# QSPIFlash.net
KiCad netlist of a schematic drawn in Altium Designer
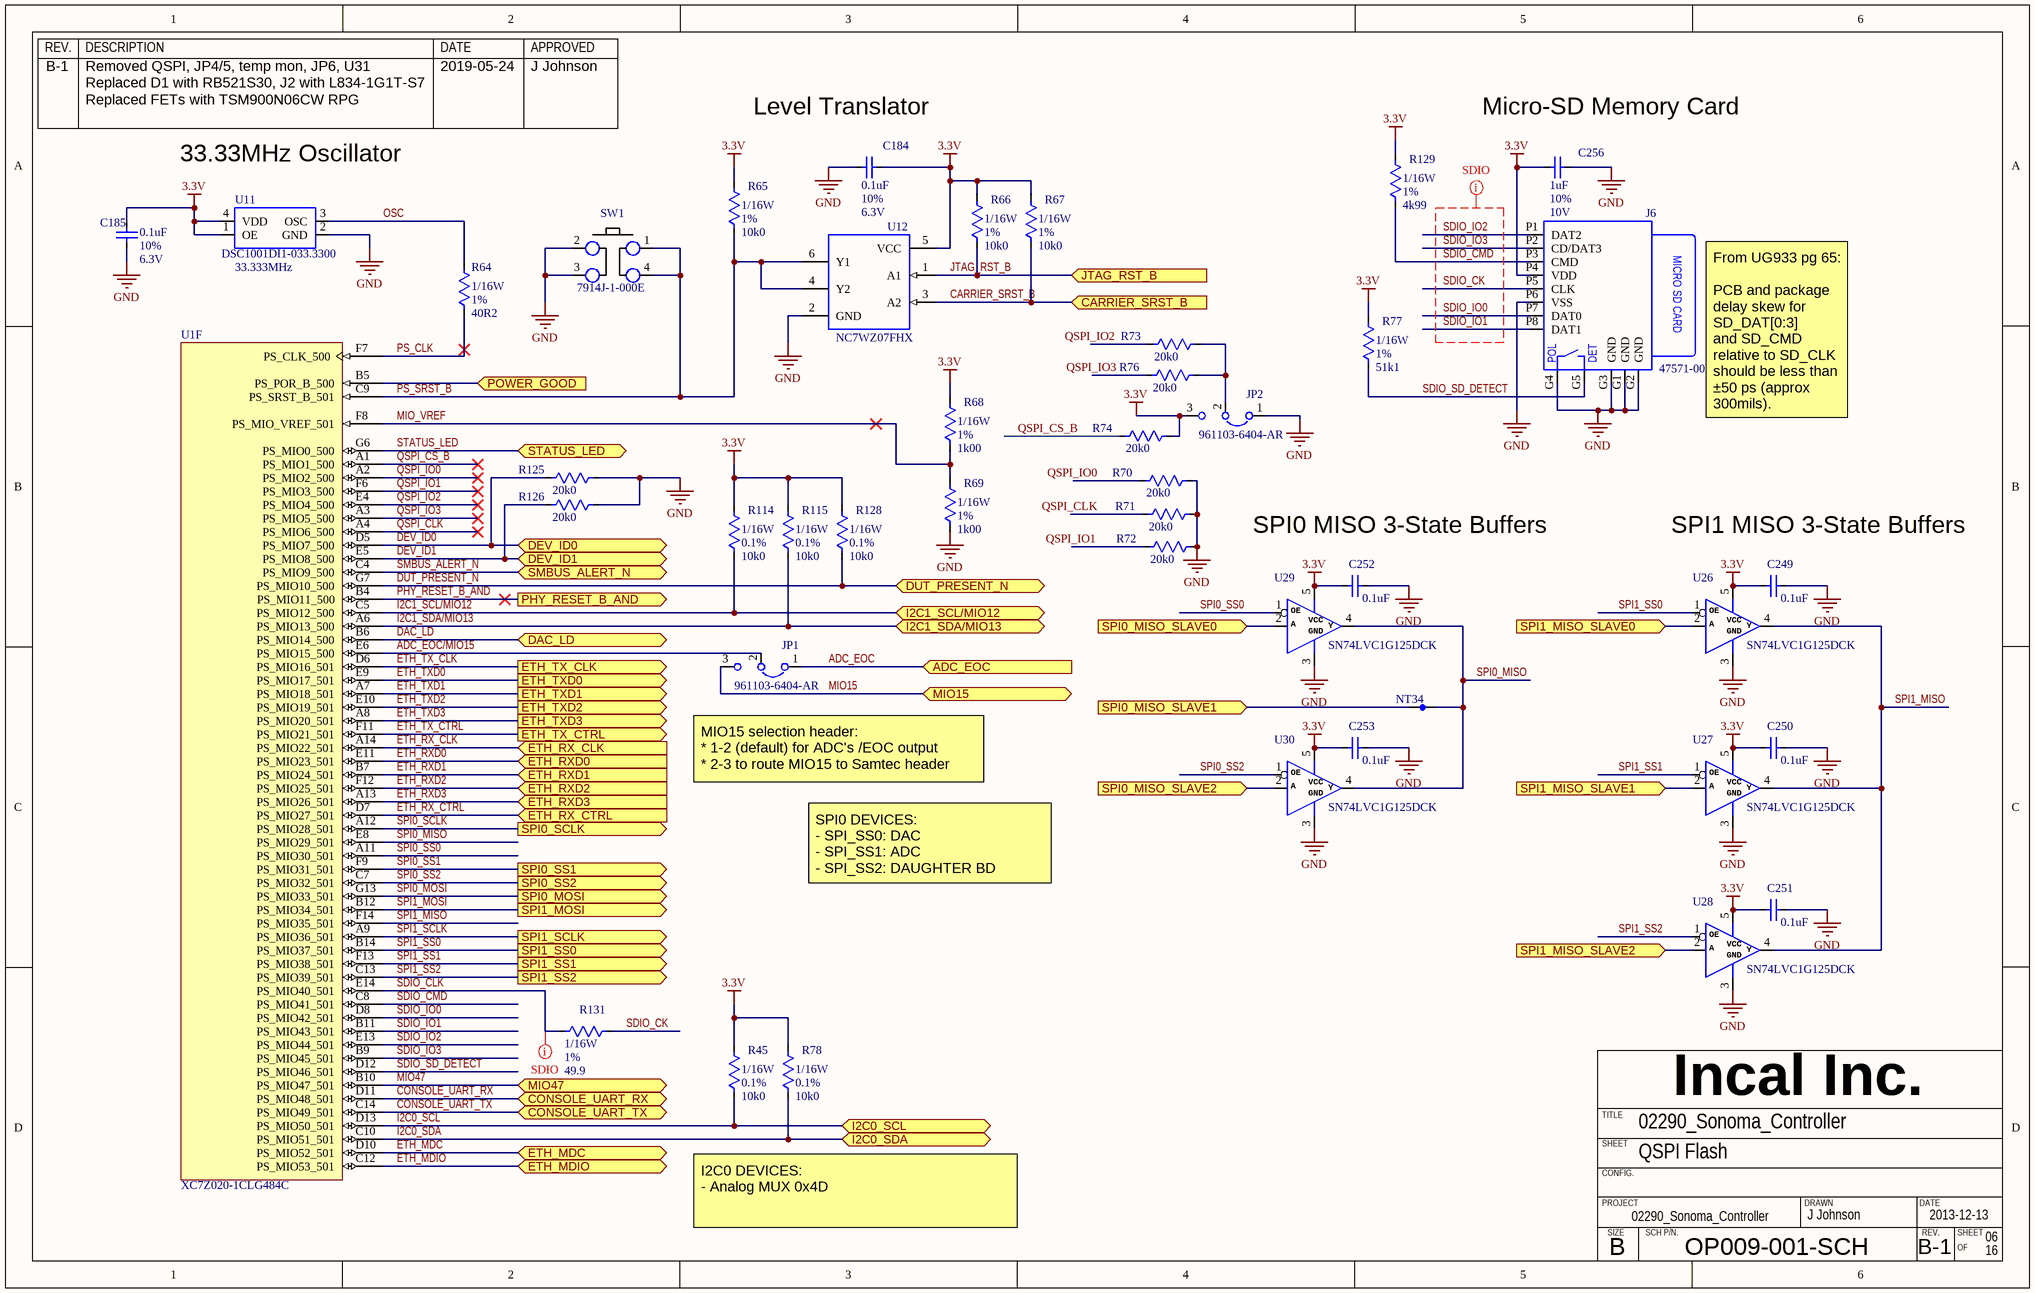
[diagram p0: QSPIFlash.SchDoc]

(export (version "E")
  (design (tool "Eeschema 10.0.6"))
  (components
    (comp (ref "C184")
      (value "0.1uF")
      (footprint "CAPC0603X33N")
      (description "Capacitor ceramic, X5R, 0.1uF, 6.3V, 10%, -55 to +125 C, EIA0201")
      (fields
        (field (name "TOLERANCE") "10%")
        (field (name "VOLTAGE") "6.3V")
        (field (name "Comment") "CAPACITOR_NP_TYPE1")
      )
      (libsource (lib "parts") (part "CAPACITOR_NP_TYPE1"))
    )
    (comp (ref "C185")
      (value "0.1uF")
      (footprint "CAPC0603X33N")
      (description "Capacitor ceramic, X5R, 0.1uF, 6.3V, 10%, -55 to +125 C, EIA0201")
      (fields
        (field (name "TOLERANCE") "10%")
        (field (name "VOLTAGE") "6.3V")
        (field (name "Comment") "CAPACITOR_NP_TYPE1")
      )
      (libsource (lib "parts") (part "CAPACITOR_NP_TYPE1"))
    )
    (comp (ref "C249")
      (value "0.1uF")
      (footprint "CAPC0603X33N")
      (description "Capacitor ceramic, X5R, 0.1uF, 6.3V, 10%, -55 to +125 C, EIA0201")
      (fields (field (name "TOLERANCE") "10%") (field (name "VOLTAGE") "6.3V"))
      (libsource (lib "parts") (part "CAPACITOR_NP_TYPE1"))
    )
    (comp (ref "C250")
      (value "0.1uF")
      (footprint "CAPC0603X33N")
      (description "Capacitor ceramic, X5R, 0.1uF, 6.3V, 10%, -55 to +125 C, EIA0201")
      (fields (field (name "TOLERANCE") "10%") (field (name "VOLTAGE") "6.3V"))
      (libsource (lib "parts") (part "CAPACITOR_NP_TYPE1"))
    )
    (comp (ref "C251")
      (value "0.1uF")
      (footprint "CAPC0603X33N")
      (description "Capacitor ceramic, X5R, 0.1uF, 6.3V, 10%, -55 to +125 C, EIA0201")
      (fields (field (name "TOLERANCE") "10%") (field (name "VOLTAGE") "6.3V"))
      (libsource (lib "parts") (part "CAPACITOR_NP_TYPE1"))
    )
    (comp (ref "C252")
      (value "0.1uF")
      (footprint "CAPC0603X33N")
      (description "Capacitor ceramic, X5R, 0.1uF, 6.3V, 10%, -55 to +125 C, EIA0201")
      (fields (field (name "TOLERANCE") "10%") (field (name "VOLTAGE") "6.3V"))
      (libsource (lib "parts") (part "CAPACITOR_NP_TYPE1"))
    )
    (comp (ref "C253")
      (value "0.1uF")
      (footprint "CAPC0603X33N")
      (description "Capacitor ceramic, X5R, 0.1uF, 6.3V, 10%, -55 to +125 C, EIA0201")
      (fields (field (name "TOLERANCE") "10%") (field (name "VOLTAGE") "6.3V"))
      (libsource (lib "parts") (part "CAPACITOR_NP_TYPE1"))
    )
    (comp (ref "C256")
      (value "1uF")
      (footprint "CAPC1005X33N")
      (description "Capacitor ceramic, X5R, 1uF, 10V, 10%, -55 to +85 C, EIA0402")
      (fields
        (field (name "TOLERANCE") "10%")
        (field (name "VOLTAGE") "10V")
        (field (name "Comment") "CAPACITOR_NP_TYPE1")
      )
      (libsource (lib "parts") (part "CAPACITOR_NP_TYPE1"))
    )
    (comp (ref "J6")
      (value "SD_MICRO_DET1")
      (footprint "47571-0001")
      (description "MicroSD Card Header with Detect, 9 pin, RA, 1.10 mm, SMT, -40 to +85C")
      (fields
        (field (name "POWER") "Pow")
        (field (name "VOLTAGE") "Vol")
        (field (name "MFG PART NUMBER 1") "47571-0001")
      )
      (libsource (lib "parts") (part "SD_MICRO_DET1"))
    )
    (comp (ref "JP1")
      (value "JP_HDR3x1_DEF1")
      (footprint "JMPR3P254_SHUNT12")
      (description "Jumper Header .100'', 3-pin, Default position 1-2, TH")
      (fields
        (field (name "POWER") "Pow")
        (field (name "VOLTAGE") "Vol")
        (field (name "MFG PART NUMBER 1") "961103-6404-AR")
      )
      (libsource (lib "parts") (part "JP_HDR3x1_DEF1"))
    )
    (comp (ref "JP2")
      (value "JP_HDR3x1_DEF1")
      (footprint "3PIN_HEADER")
      (description "Jumper Header .100'', 3-pin, Default position 1-2, TH")
      (fields
        (field (name "POWER") "Pow")
        (field (name "VOLTAGE") "Vol")
        (field (name "MFG PART NUMBER 1") "961103-6404-AR")
      )
      (libsource (lib "parts") (part "JP_HDR3x1_DEF1"))
    )
    (comp (ref "NT34")
      (value "NET_TIE_1X1")
      (footprint "NET_TIE_1X1")
      (description "Net Tie 1 to 1")
      (libsource (lib "parts") (part "NET_TIE_1X1"))
    )
    (comp (ref "R45")
      (value "10k0")
      (footprint "RESC1005X33N")
      (description "Resistor, 10k0, 1/16W, 0.1%, -50 to +155 C, EIA0402")
      (fields (field (name "VOLTAGE") "50V") (field (name "POWER") "1/16W") (field (name "TOLERANCE") "0.1%"))
      (libsource (lib "parts") (part "RESISTOR_TYPE1"))
    )
    (comp (ref "R64")
      (value "40R2")
      (footprint "RESC1005X33N")
      (description "Resistor, 40R2, 1/16W, 1%, -50 to +155 C, EIA0402, EIA(M)1005")
      (fields (field (name "VOLTAGE") "50V") (field (name "POWER") "1/16W") (field (name "TOLERANCE") "1%"))
      (libsource (lib "parts") (part "RESISTOR_TYPE1"))
    )
    (comp (ref "R65")
      (value "10k0")
      (footprint "RESC1005X33N")
      (description "Resistor, 10k0, 1/16W, 1%, -55 to +155 C, EIA0402")
      (fields (field (name "VOLTAGE") "50V") (field (name "POWER") "1/16W") (field (name "TOLERANCE") "1%"))
      (libsource (lib "parts") (part "RESISTOR_TYPE1"))
    )
    (comp (ref "R66")
      (value "10k0")
      (footprint "RESC1005X33N")
      (description "Resistor, 10k0, 1/16W, 1%, -55 to +155 C, EIA0402")
      (fields (field (name "VOLTAGE") "50V") (field (name "POWER") "1/16W") (field (name "TOLERANCE") "1%"))
      (libsource (lib "parts") (part "RESISTOR_TYPE1"))
    )
    (comp (ref "R67")
      (value "10k0")
      (footprint "RESC1005X33N")
      (description "Resistor, 10k0, 1/16W, 1%, -55 to +155 C, EIA0402")
      (fields (field (name "VOLTAGE") "50V") (field (name "POWER") "1/16W") (field (name "TOLERANCE") "1%"))
      (libsource (lib "parts") (part "RESISTOR_TYPE1"))
    )
    (comp (ref "R68")
      (value "1k00")
      (footprint "RESC1005X33N")
      (description "Resistor, 1k00, 1/16W, 1%, -55 to +155 C, EIA0402")
      (fields (field (name "VOLTAGE") "50V") (field (name "POWER") "1/16W") (field (name "TOLERANCE") "1%"))
      (libsource (lib "parts") (part "RESISTOR_TYPE1"))
    )
    (comp (ref "R69")
      (value "1k00")
      (footprint "RESC1005X33N")
      (description "Resistor, 1k00, 1/16W, 1%, -55 to +155 C, EIA0402")
      (fields (field (name "VOLTAGE") "50V") (field (name "POWER") "1/16W") (field (name "TOLERANCE") "1%"))
      (libsource (lib "parts") (part "RESISTOR_TYPE1"))
    )
    (comp (ref "R70")
      (value "20k0")
      (footprint "0402")
      (description "Resistor, 20k0, 1/16W, 1%, -50 to +155 C, EIA0402, EIA(M)1005")
      (fields (field (name "VOLTAGE") "50V") (field (name "POWER") "1/16W"))
      (libsource (lib "parts") (part "RESISTOR_TYPE1"))
    )
    (comp (ref "R71")
      (value "20k0")
      (footprint "0402")
      (description "Resistor, 20k0, 1/16W, 1%, -50 to +155 C, EIA0402, EIA(M)1005")
      (fields (field (name "VOLTAGE") "50V") (field (name "POWER") "1/16W"))
      (libsource (lib "parts") (part "RESISTOR_TYPE1"))
    )
    (comp (ref "R72")
      (value "20k0")
      (footprint "RESC1005X33N")
      (description "Resistor, 20k0, 1/16W, 1%, -50 to +155 C, EIA0402, EIA(M)1005")
      (fields (field (name "VOLTAGE") "50V") (field (name "POWER") "1/16W"))
      (libsource (lib "parts") (part "RESISTOR_TYPE1"))
    )
    (comp (ref "R73")
      (value "20k0")
      (footprint "0402")
      (description "Resistor, 20k0, 1/16W, 1%, -50 to +155 C, EIA0402, EIA(M)1005")
      (fields (field (name "VOLTAGE") "50V") (field (name "POWER") "1/16W"))
      (libsource (lib "parts") (part "RESISTOR_TYPE1"))
    )
    (comp (ref "R74")
      (value "20k0")
      (footprint "0402")
      (description "Resistor, 20k0, 1/16W, 1%, -50 to +155 C, EIA0402, EIA(M)1005")
      (fields (field (name "VOLTAGE") "50V") (field (name "POWER") "1/16W"))
      (libsource (lib "parts") (part "RESISTOR_TYPE1"))
    )
    (comp (ref "R76")
      (value "20k0")
      (footprint "0402")
      (description "Resistor, 20k0, 1/16W, 1%, -50 to +155 C, EIA0402, EIA(M)1005")
      (fields (field (name "VOLTAGE") "50V") (field (name "POWER") "1/16W"))
      (libsource (lib "parts") (part "RESISTOR_TYPE1"))
    )
    (comp (ref "R77")
      (value "51k1")
      (footprint "RESC1005X33N")
      (description "Resistor, 51k1, 1/16W, 1%, -50 to +155 C, EIA0402, EIA(M)1005")
      (fields (field (name "VOLTAGE") "50V") (field (name "POWER") "1/16W") (field (name "TOLERANCE") "1%"))
      (libsource (lib "parts") (part "RESISTOR_TYPE1"))
    )
    (comp (ref "R78")
      (value "10k0")
      (footprint "RESC1005X33N")
      (description "Resistor, 10k0, 1/16W, 0.1%, -50 to +155 C, EIA0402")
      (fields (field (name "VOLTAGE") "50V") (field (name "POWER") "1/16W") (field (name "TOLERANCE") "0.1%"))
      (libsource (lib "parts") (part "RESISTOR_TYPE1"))
    )
    (comp (ref "R114")
      (value "10k0")
      (footprint "RESC1005X33N")
      (description "Resistor, 10k0, 1/16W, 0.1%, -50 to +155 C, EIA0402")
      (fields (field (name "VOLTAGE") "50V") (field (name "POWER") "1/16W") (field (name "TOLERANCE") "0.1%"))
      (libsource (lib "parts") (part "RESISTOR_TYPE1"))
    )
    (comp (ref "R115")
      (value "10k0")
      (footprint "RESC1005X33N")
      (description "Resistor, 10k0, 1/16W, 0.1%, -50 to +155 C, EIA0402")
      (fields (field (name "VOLTAGE") "50V") (field (name "POWER") "1/16W") (field (name "TOLERANCE") "0.1%"))
      (libsource (lib "parts") (part "RESISTOR_TYPE1"))
    )
    (comp (ref "R125")
      (value "20k0")
      (footprint "RESC1005X33N")
      (description "Resistor, 20k0, 1/16W, 1%, -50 to +155 C, EIA0402, EIA(M)1005")
      (fields (field (name "VOLTAGE") "50V") (field (name "POWER") "1/16W"))
      (libsource (lib "parts") (part "RESISTOR_TYPE1"))
    )
    (comp (ref "R126")
      (value "20k0")
      (footprint "RESC1005X33N")
      (description "Resistor, 20k0, 1/16W, 1%, -50 to +155 C, EIA0402, EIA(M)1005")
      (fields (field (name "VOLTAGE") "50V") (field (name "POWER") "1/16W"))
      (libsource (lib "parts") (part "RESISTOR_TYPE1"))
    )
    (comp (ref "R128")
      (value "10k0")
      (footprint "RESC1005X33N")
      (description "Resistor, 10k0, 1/16W, 0.1%, -50 to +155 C, EIA0402")
      (fields (field (name "VOLTAGE") "50V") (field (name "POWER") "1/16W") (field (name "TOLERANCE") "0.1%"))
      (libsource (lib "parts") (part "RESISTOR_TYPE1"))
    )
    (comp (ref "R129")
      (value "4k99")
      (footprint "RESC1005X33N")
      (description "Resistor, 4k99, 1/16W, 1%, -50 to +155 C, EIA0402, EIA(M)1005")
      (fields (field (name "VOLTAGE") "50V") (field (name "POWER") "1/16W") (field (name "TOLERANCE") "1%"))
      (libsource (lib "parts") (part "RESISTOR_TYPE1"))
    )
    (comp (ref "R131")
      (value "49.9")
      (footprint "RESC1005X33N")
      (description "Resistor, 51k1, 1/16W, 1%, -50 to +155 C, EIA0402, EIA(M)1005")
      (fields (field (name "VOLTAGE") "50V") (field (name "POWER") "1/16W") (field (name "TOLERANCE") "1%"))
      (libsource (lib "parts") (part "RESISTOR_TYPE1"))
    )
    (comp (ref "SW1")
      (value "7914J-1-000E")
      (footprint "7914J-1-000E")
      (description "Switch, tactile, 39V, 4mm, -55 to +125 C, SMD")
      (fields (field (name "POWER") "Pow") (field (name "VOLTAGE") "39V"))
      (libsource (lib "parts") (part "SW_SPST_TYPE1"))
    )
    (comp (ref "U1")
      (value "XC7Z020-1CLG484C")
      (footprint "CLG484")
      (description "667 MHz Zynq™-7000 AP SoC, 130 PS I/O, 200 FPGA I/O, 484-Ball BGA, Speed Grade 1, Commercial Grade")
      (fields (field (name "GENERIC PART NUMBER") "XC7Z020") (field (name "MANUFACTURER") "Xilinx"))
      (libsource (lib "parts") (part "XC7Z020-1CLG484C"))
    )
    (comp (ref "U11")
      (value "33.333MHz")
      (footprint "OSCSC165P200X250X85-4N")
      (description "Oscillator, CMOS, 33.333MHz, 50ppm, 1.7V to 3.6V, -40 to +85C, SMT")
      (fields
        (field (name "VOLTAGE") "1.7V to 3.6V")
        (field (name "MFG PART NUMBER 1") "DSC1001DI1-033.3300")
        (field (name "Comment") "OSCILLATOR_TYPE1")
      )
      (libsource (lib "parts") (part "OSCILLATOR_TYPE1"))
    )
    (comp (ref "U12")
      (value "NC7WZ07FHX")
      (footprint "DFN35P100X100X55-6N")
      (description "UHS Dual Buffer, Tiny Logic, 1.65 to 5.5V, -40 to +85 C, 200mW, MicroPak2-6")
      (fields
        (field (name "POWER") "Pow")
        (field (name "VOLTAGE") "1.65 to 5.5V")
        (field (name "MFG PART NUMBER 1") "NC7WZ07FHX")
      )
      (libsource (lib "parts") (part "NC7WZ07FHX"))
    )
    (comp (ref "U26")
      (value "SN74LVC1G125DCK")
      (footprint "SOT65P210X110-5N")
      (description "Tristate buffer, 1.65 to 5.5V, +/- 24mA, -40 to +125 C, 150mW, SC70")
      (fields (field (name "POWER") "150mW") (field (name "VOLTAGE") "1.65 to 5.5V"))
      (libsource (lib "parts") (part "TINY_SCHM_BUF_TRIS_TYPE1"))
    )
    (comp (ref "U27")
      (value "SN74LVC1G125DCK")
      (footprint "SOT65P210X110-5N")
      (description "Tristate buffer, 1.65 to 5.5V, +/- 24mA, -40 to +125 C, 150mW, SC70")
      (fields (field (name "POWER") "150mW") (field (name "VOLTAGE") "1.65 to 5.5V"))
      (libsource (lib "parts") (part "TINY_SCHM_BUF_TRIS_TYPE1"))
    )
    (comp (ref "U28")
      (value "SN74LVC1G125DCK")
      (footprint "SOT65P210X110-5N")
      (description "Tristate buffer, 1.65 to 5.5V, +/- 24mA, -40 to +125 C, 150mW, SC70")
      (fields (field (name "POWER") "150mW") (field (name "VOLTAGE") "1.65 to 5.5V"))
      (libsource (lib "parts") (part "TINY_SCHM_BUF_TRIS_TYPE1"))
    )
    (comp (ref "U29")
      (value "SN74LVC1G125DCK")
      (footprint "SOT65P210X110-5N")
      (description "Tristate buffer, 1.65 to 5.5V, +/- 24mA, -40 to +125 C, 150mW, SC70")
      (fields (field (name "POWER") "150mW") (field (name "VOLTAGE") "1.65 to 5.5V"))
      (libsource (lib "parts") (part "TINY_SCHM_BUF_TRIS_TYPE1"))
    )
    (comp (ref "U30")
      (value "SN74LVC1G125DCK")
      (footprint "SOT65P210X110-5N")
      (description "Tristate buffer, 1.65 to 5.5V, +/- 24mA, -40 to +125 C, 150mW, SC70")
      (fields (field (name "POWER") "150mW") (field (name "VOLTAGE") "1.65 to 5.5V"))
      (libsource (lib "parts") (part "TINY_SCHM_BUF_TRIS_TYPE1"))
    )
  )
  (nets
    (net (code "1") (name "/ADC_EOC") (class "Default") (node (ref "JP1") (pin "1") (pintype "passive")))
    (net (code "2") (name "/ADC_EOC{slash}MIO15") (class "Default")
      (node (ref "JP1") (pin "2") (pintype "passive"))
      (node (ref "U1") (pin "E6") (pinfunction "PS_MIO15_500_E6") (pintype "bidirectional"))
    )
    (net (code "3") (name "/CARRIER_SRST_B") (class "Default")
      (node (ref "R67") (pin "1") (pinfunction "1_1") (pintype "passive"))
      (node (ref "U12") (pin "3") (pinfunction "A2_3") (pintype "input"))
    )
    (net (code "4") (name "/CONSOLE_UART_RX") (class "Default")
      (node (ref "U1") (pin "D11") (pinfunction "PS_MIO48_501_D11") (pintype "bidirectional"))
    )
    (net (code "5") (name "/CONSOLE_UART_TX") (class "Default")
      (node (ref "U1") (pin "C14") (pinfunction "PS_MIO49_501_C14") (pintype "bidirectional"))
    )
    (net (code "6") (name "/DAC_LD") (class "Default")
      (node (ref "U1") (pin "B6") (pinfunction "PS_MIO14_500_B6") (pintype "bidirectional"))
    )
    (net (code "7") (name "/DEV_ID0") (class "Default")
      (node (ref "R125") (pin "1") (pinfunction "1_1") (pintype "passive"))
      (node (ref "U1") (pin "D5") (pinfunction "PS_MIO7_500_D5") (pintype "bidirectional"))
    )
    (net (code "8") (name "/DEV_ID1") (class "Default")
      (node (ref "R126") (pin "1") (pinfunction "1_1") (pintype "passive"))
      (node (ref "U1") (pin "E5") (pinfunction "PS_MIO8_500_E5") (pintype "bidirectional"))
    )
    (net (code "9") (name "/DUT_PRESENT_N") (class "Default")
      (node (ref "R128") (pin "2") (pinfunction "2_2") (pintype "passive"))
      (node (ref "U1") (pin "G7") (pinfunction "PS_MIO10_500_G7") (pintype "bidirectional"))
    )
    (net (code "10") (name "/ETH_MDC") (class "Default")
      (node (ref "U1") (pin "D10") (pinfunction "PS_MIO52_501_D10") (pintype "bidirectional"))
    )
    (net (code "11") (name "/ETH_MDIO") (class "Default")
      (node (ref "U1") (pin "C12") (pinfunction "PS_MIO53_501_C12") (pintype "bidirectional"))
    )
    (net (code "12") (name "/ETH_RXD0") (class "Default")
      (node (ref "U1") (pin "E11") (pinfunction "PS_MIO23_501_E11") (pintype "bidirectional"))
    )
    (net (code "13") (name "/ETH_RXD1") (class "Default")
      (node (ref "U1") (pin "B7") (pinfunction "PS_MIO24_501_B7") (pintype "bidirectional"))
    )
    (net (code "14") (name "/ETH_RXD2") (class "Default")
      (node (ref "U1") (pin "F12") (pinfunction "PS_MIO25_501_F12") (pintype "bidirectional"))
    )
    (net (code "15") (name "/ETH_RXD3") (class "Default")
      (node (ref "U1") (pin "A13") (pinfunction "PS_MIO26_501_A13") (pintype "bidirectional"))
    )
    (net (code "16") (name "/ETH_RX_CLK") (class "Default")
      (node (ref "U1") (pin "A14") (pinfunction "PS_MIO22_501_A14") (pintype "bidirectional"))
    )
    (net (code "17") (name "/ETH_RX_CTRL") (class "Default")
      (node (ref "U1") (pin "D7") (pinfunction "PS_MIO27_501_D7") (pintype "bidirectional"))
    )
    (net (code "18") (name "/ETH_TXD0") (class "Default")
      (node (ref "U1") (pin "E9") (pinfunction "PS_MIO17_501_E9") (pintype "bidirectional"))
    )
    (net (code "19") (name "/ETH_TXD1") (class "Default")
      (node (ref "U1") (pin "A7") (pinfunction "PS_MIO18_501_A7") (pintype "bidirectional"))
    )
    (net (code "20") (name "/ETH_TXD2") (class "Default")
      (node (ref "U1") (pin "E10") (pinfunction "PS_MIO19_501_E10") (pintype "bidirectional"))
    )
    (net (code "21") (name "/ETH_TXD3") (class "Default")
      (node (ref "U1") (pin "A8") (pinfunction "PS_MIO20_501_A8") (pintype "bidirectional"))
    )
    (net (code "22") (name "/ETH_TX_CLK") (class "Default")
      (node (ref "U1") (pin "D6") (pinfunction "PS_MIO16_501_D6") (pintype "bidirectional"))
    )
    (net (code "23") (name "/ETH_TX_CTRL") (class "Default")
      (node (ref "U1") (pin "F11") (pinfunction "PS_MIO21_501_F11") (pintype "bidirectional"))
    )
    (net (code "24") (name "/I2C0_SCL") (class "Default")
      (node (ref "R45") (pin "2") (pinfunction "2_2") (pintype "passive"))
      (node (ref "U1") (pin "D13") (pinfunction "PS_MIO50_501_D13") (pintype "bidirectional"))
    )
    (net (code "25") (name "/I2C0_SDA") (class "Default")
      (node (ref "R78") (pin "2") (pinfunction "2_2") (pintype "passive"))
      (node (ref "U1") (pin "C10") (pinfunction "PS_MIO51_501_C10") (pintype "bidirectional"))
    )
    (net (code "26") (name "/I2C1_SCL{slash}MIO12") (class "Default")
      (node (ref "R114") (pin "2") (pinfunction "2_2") (pintype "passive"))
      (node (ref "U1") (pin "C5") (pinfunction "PS_MIO12_500_C5") (pintype "bidirectional"))
    )
    (net (code "27") (name "/I2C1_SDA{slash}MIO13") (class "Default")
      (node (ref "R115") (pin "2") (pinfunction "2_2") (pintype "passive"))
      (node (ref "U1") (pin "A6") (pinfunction "PS_MIO13_500_A6") (pintype "bidirectional"))
    )
    (net (code "28") (name "/JTAG_RST_B") (class "Default")
      (node (ref "R66") (pin "1") (pinfunction "1_1") (pintype "passive"))
      (node (ref "U12") (pin "1") (pinfunction "A1_1") (pintype "input"))
    )
    (net (code "29") (name "/MIO15") (class "Default") (node (ref "JP1") (pin "3") (pintype "passive")))
    (net (code "30") (name "/MIO47") (class "Default")
      (node (ref "U1") (pin "B10") (pinfunction "PS_MIO47_501_B10") (pintype "bidirectional"))
    )
    (net (code "31") (name "/MIO_VREF") (class "Default")
      (node (ref "R68") (pin "2") (pinfunction "2_2") (pintype "passive"))
      (node (ref "R69") (pin "1") (pinfunction "1_1") (pintype "passive"))
      (node (ref "U1") (pin "F8") (pinfunction "PS_MIO_VREF_501_F8") (pintype "input"))
    )
    (net (code "32") (name "/OSC") (class "Default")
      (node (ref "R64") (pin "1") (pinfunction "1_1") (pintype "passive"))
      (node (ref "U11") (pin "3") (pinfunction "OSC_3") (pintype "passive"))
    )
    (net (code "33") (name "/PHY_RESET_B_AND") (class "Default")
      (node (ref "U1") (pin "B4") (pinfunction "PS_MIO11_500_B4") (pintype "bidirectional"))
    )
    (net (code "34") (name "/POWER_GOOD") (class "Default")
      (node (ref "U1") (pin "B5") (pinfunction "PS_POR_B_500_B5") (pintype "input"))
    )
    (net (code "35") (name "/PS_CLK") (class "Default")
      (node (ref "R64") (pin "2") (pinfunction "2_2") (pintype "passive"))
      (node (ref "U1") (pin "F7") (pinfunction "PS_CLK_500_F7") (pintype "input"))
    )
    (net (code "36") (name "/PS_SRST_B") (class "Default")
      (node (ref "R65") (pin "1") (pinfunction "1_1") (pintype "passive"))
      (node (ref "SW1") (pin "1") (pinfunction "1_1") (pintype "passive"))
      (node (ref "SW1") (pin "4") (pinfunction "4_4") (pintype "passive"))
      (node (ref "U1") (pin "C9") (pinfunction "PS_SRST_B_501_C9") (pintype "input"))
      (node (ref "U12") (pin "4") (pinfunction "Y2_4") (pintype "open_collector"))
      (node (ref "U12") (pin "6") (pinfunction "Y1_6") (pintype "open_collector"))
    )
    (net (code "37") (name "/QSPI_CLK") (class "Default")
      (node (ref "R71") (pin "1") (pinfunction "1_1") (pintype "passive"))
      (node (ref "U1") (pin "A4") (pinfunction "PS_MIO6_500_A4") (pintype "bidirectional"))
    )
    (net (code "38") (name "/QSPI_CS_B") (class "Default")
      (node (ref "R74") (pin "1") (pinfunction "1_1") (pintype "passive"))
      (node (ref "U1") (pin "A1") (pinfunction "PS_MIO1_500_A1") (pintype "bidirectional"))
    )
    (net (code "39") (name "/QSPI_IO0") (class "Default")
      (node (ref "R70") (pin "1") (pinfunction "1_1") (pintype "passive"))
      (node (ref "U1") (pin "A2") (pinfunction "PS_MIO2_500_A2") (pintype "bidirectional"))
    )
    (net (code "40") (name "/QSPI_IO1") (class "Default")
      (node (ref "R72") (pin "1") (pinfunction "1_1") (pintype "passive"))
      (node (ref "U1") (pin "F6") (pinfunction "PS_MIO3_500_F6") (pintype "bidirectional"))
    )
    (net (code "41") (name "/QSPI_IO2") (class "Default")
      (node (ref "R73") (pin "1") (pinfunction "1_1") (pintype "passive"))
      (node (ref "U1") (pin "E4") (pinfunction "PS_MIO4_500_E4") (pintype "bidirectional"))
    )
    (net (code "42") (name "/QSPI_IO3") (class "Default")
      (node (ref "R76") (pin "1") (pinfunction "1_1") (pintype "passive"))
      (node (ref "U1") (pin "A3") (pinfunction "PS_MIO5_500_A3") (pintype "bidirectional"))
    )
    (net (code "43") (name "/SDIO_CK") (class "Default")
      (node (ref "J6") (pin "P5") (pinfunction "CLK_P5") (pintype "passive"))
      (node (ref "R131") (pin "2") (pinfunction "2_2") (pintype "passive"))
    )
    (net (code "44") (name "/SDIO_CLK") (class "Default")
      (node (ref "R131") (pin "1") (pinfunction "1_1") (pintype "passive"))
      (node (ref "U1") (pin "E14") (pinfunction "PS_MIO40_501_E14") (pintype "bidirectional"))
    )
    (net (code "45") (name "/SDIO_CMD") (class "Default")
      (node (ref "J6") (pin "P3") (pinfunction "CMD_P3") (pintype "passive"))
      (node (ref "R129") (pin "2") (pinfunction "2_2") (pintype "passive"))
      (node (ref "U1") (pin "C8") (pinfunction "PS_MIO41_501_C8") (pintype "bidirectional"))
    )
    (net (code "46") (name "/SDIO_IO0") (class "Default")
      (node (ref "J6") (pin "P7") (pinfunction "DAT0_P7") (pintype "passive"))
      (node (ref "U1") (pin "D8") (pinfunction "PS_MIO42_501_D8") (pintype "bidirectional"))
    )
    (net (code "47") (name "/SDIO_IO1") (class "Default")
      (node (ref "J6") (pin "P8") (pinfunction "DAT1_P8") (pintype "passive"))
      (node (ref "U1") (pin "B11") (pinfunction "PS_MIO43_501_B11") (pintype "bidirectional"))
    )
    (net (code "48") (name "/SDIO_IO2") (class "Default")
      (node (ref "J6") (pin "P1") (pinfunction "DAT2_P1") (pintype "passive"))
      (node (ref "U1") (pin "E13") (pinfunction "PS_MIO44_501_E13") (pintype "bidirectional"))
    )
    (net (code "49") (name "/SDIO_IO3") (class "Default")
      (node (ref "J6") (pin "P2") (pinfunction "CD/DAT3_P2") (pintype "passive"))
      (node (ref "U1") (pin "B9") (pinfunction "PS_MIO45_501_B9") (pintype "bidirectional"))
    )
    (net (code "50") (name "/SDIO_SD_DETECT") (class "Default")
      (node (ref "J6") (pin "G5") (pinfunction "DET_G5") (pintype "passive"))
      (node (ref "R77") (pin "2") (pinfunction "2_2") (pintype "passive"))
      (node (ref "U1") (pin "D12") (pinfunction "PS_MIO46_501_D12") (pintype "bidirectional"))
    )
    (net (code "51") (name "/SMBUS_ALERT_N") (class "Default")
      (node (ref "U1") (pin "C4") (pinfunction "PS_MIO9_500_C4") (pintype "bidirectional"))
    )
    (net (code "52") (name "/SPI0_MISO") (class "Default")
      (node (ref "NT34") (pin "2") (pinfunction "2_2") (pintype "passive"))
      (node (ref "U1") (pin "E8") (pinfunction "PS_MIO29_501_E8") (pintype "bidirectional"))
      (node (ref "U29") (pin "4") (pinfunction "Y_4") (pintype "passive"))
      (node (ref "U30") (pin "4") (pinfunction "Y_4") (pintype "passive"))
    )
    (net (code "53") (name "/SPI0_MISO_SLAVE0") (class "Default")
      (node (ref "U29") (pin "2") (pinfunction "A_2") (pintype "passive"))
    )
    (net (code "54") (name "/SPI0_MISO_SLAVE1") (class "Default")
      (node (ref "NT34") (pin "1") (pinfunction "1_1") (pintype "passive"))
    )
    (net (code "55") (name "/SPI0_MISO_SLAVE2") (class "Default")
      (node (ref "U30") (pin "2") (pinfunction "A_2") (pintype "passive"))
    )
    (net (code "56") (name "/SPI0_MOSI") (class "Default")
      (node (ref "U1") (pin "G13") (pinfunction "PS_MIO33_501_G13") (pintype "bidirectional"))
    )
    (net (code "57") (name "/SPI0_SCLK") (class "Default")
      (node (ref "U1") (pin "A12") (pinfunction "PS_MIO28_501_A12") (pintype "bidirectional"))
    )
    (net (code "58") (name "/SPI0_SS0") (class "Default")
      (node (ref "U1") (pin "A11") (pinfunction "PS_MIO30_501_A11") (pintype "bidirectional"))
      (node (ref "U29") (pin "1") (pinfunction "OE_1") (pintype "passive"))
    )
    (net (code "59") (name "/SPI0_SS1") (class "Default")
      (node (ref "U1") (pin "F9") (pinfunction "PS_MIO31_501_F9") (pintype "bidirectional"))
    )
    (net (code "60") (name "/SPI0_SS2") (class "Default")
      (node (ref "U1") (pin "C7") (pinfunction "PS_MIO32_501_C7") (pintype "bidirectional"))
      (node (ref "U30") (pin "1") (pinfunction "OE_1") (pintype "passive"))
    )
    (net (code "61") (name "/SPI1_MISO") (class "Default")
      (node (ref "U1") (pin "F14") (pinfunction "PS_MIO35_501_F14") (pintype "bidirectional"))
      (node (ref "U26") (pin "4") (pinfunction "Y_4") (pintype "passive"))
      (node (ref "U27") (pin "4") (pinfunction "Y_4") (pintype "passive"))
      (node (ref "U28") (pin "4") (pinfunction "Y_4") (pintype "passive"))
    )
    (net (code "62") (name "/SPI1_MISO_SLAVE0") (class "Default")
      (node (ref "U26") (pin "2") (pinfunction "A_2") (pintype "passive"))
    )
    (net (code "63") (name "/SPI1_MISO_SLAVE1") (class "Default")
      (node (ref "U27") (pin "2") (pinfunction "A_2") (pintype "passive"))
    )
    (net (code "64") (name "/SPI1_MISO_SLAVE2") (class "Default")
      (node (ref "U28") (pin "2") (pinfunction "A_2") (pintype "passive"))
    )
    (net (code "65") (name "/SPI1_MOSI") (class "Default")
      (node (ref "U1") (pin "B12") (pinfunction "PS_MIO34_501_B12") (pintype "bidirectional"))
    )
    (net (code "66") (name "/SPI1_SCLK") (class "Default")
      (node (ref "U1") (pin "A9") (pinfunction "PS_MIO36_501_A9") (pintype "bidirectional"))
    )
    (net (code "67") (name "/SPI1_SS0") (class "Default")
      (node (ref "U1") (pin "B14") (pinfunction "PS_MIO37_501_B14") (pintype "bidirectional"))
      (node (ref "U26") (pin "1") (pinfunction "OE_1") (pintype "passive"))
    )
    (net (code "68") (name "/SPI1_SS1") (class "Default")
      (node (ref "U1") (pin "F13") (pinfunction "PS_MIO38_501_F13") (pintype "bidirectional"))
      (node (ref "U27") (pin "1") (pinfunction "OE_1") (pintype "passive"))
    )
    (net (code "69") (name "/SPI1_SS2") (class "Default")
      (node (ref "U1") (pin "C13") (pinfunction "PS_MIO39_501_C13") (pintype "bidirectional"))
      (node (ref "U28") (pin "1") (pinfunction "OE_1") (pintype "passive"))
    )
    (net (code "70") (name "/STATUS_LED") (class "Default")
      (node (ref "U1") (pin "G6") (pinfunction "PS_MIO0_500_G6") (pintype "bidirectional"))
    )
    (net (code "71") (name "3.3V") (class "Default")
      (node (ref "C184") (pin "1") (pinfunction "1_1") (pintype "passive"))
      (node (ref "C185") (pin "1") (pinfunction "1_1") (pintype "passive"))
      (node (ref "C249") (pin "1") (pinfunction "1_1") (pintype "passive"))
      (node (ref "C250") (pin "1") (pinfunction "1_1") (pintype "passive"))
      (node (ref "C251") (pin "1") (pinfunction "1_1") (pintype "passive"))
      (node (ref "C252") (pin "1") (pinfunction "1_1") (pintype "passive"))
      (node (ref "C253") (pin "1") (pinfunction "1_1") (pintype "passive"))
      (node (ref "C256") (pin "1") (pinfunction "1_1") (pintype "passive"))
      (node (ref "J6") (pin "P4") (pinfunction "VDD_P4") (pintype "passive"))
      (node (ref "JP2") (pin "3") (pintype "passive"))
      (node (ref "R114") (pin "1") (pinfunction "1_1") (pintype "passive"))
      (node (ref "R115") (pin "1") (pinfunction "1_1") (pintype "passive"))
      (node (ref "R128") (pin "1") (pinfunction "1_1") (pintype "passive"))
      (node (ref "R129") (pin "1") (pinfunction "1_1") (pintype "passive"))
      (node (ref "R45") (pin "1") (pinfunction "1_1") (pintype "passive"))
      (node (ref "R65") (pin "2") (pinfunction "2_2") (pintype "passive"))
      (node (ref "R66") (pin "2") (pinfunction "2_2") (pintype "passive"))
      (node (ref "R67") (pin "2") (pinfunction "2_2") (pintype "passive"))
      (node (ref "R68") (pin "1") (pinfunction "1_1") (pintype "passive"))
      (node (ref "R74") (pin "2") (pinfunction "2_2") (pintype "passive"))
      (node (ref "R77") (pin "1") (pinfunction "1_1") (pintype "passive"))
      (node (ref "R78") (pin "1") (pinfunction "1_1") (pintype "passive"))
      (node (ref "U11") (pin "1") (pinfunction "OE_1") (pintype "passive"))
      (node (ref "U11") (pin "4") (pinfunction "VDD_4") (pintype "passive"))
      (node (ref "U12") (pin "5") (pinfunction "VCC_5") (pintype "power_in"))
      (node (ref "U26") (pin "5") (pinfunction "VCC_5") (pintype "passive"))
      (node (ref "U27") (pin "5") (pinfunction "VCC_5") (pintype "passive"))
      (node (ref "U28") (pin "5") (pinfunction "VCC_5") (pintype "passive"))
      (node (ref "U29") (pin "5") (pinfunction "VCC_5") (pintype "passive"))
      (node (ref "U30") (pin "5") (pinfunction "VCC_5") (pintype "passive"))
    )
    (net (code "72") (name "GND") (class "Default")
      (node (ref "C184") (pin "2") (pinfunction "2_2") (pintype "passive"))
      (node (ref "C185") (pin "2") (pinfunction "2_2") (pintype "passive"))
      (node (ref "C249") (pin "2") (pinfunction "2_2") (pintype "passive"))
      (node (ref "C250") (pin "2") (pinfunction "2_2") (pintype "passive"))
      (node (ref "C251") (pin "2") (pinfunction "2_2") (pintype "passive"))
      (node (ref "C252") (pin "2") (pinfunction "2_2") (pintype "passive"))
      (node (ref "C253") (pin "2") (pinfunction "2_2") (pintype "passive"))
      (node (ref "C256") (pin "2") (pinfunction "2_2") (pintype "passive"))
      (node (ref "J6") (pin "G1") (pinfunction "GND_G1") (pintype "passive"))
      (node (ref "J6") (pin "G2") (pinfunction "GND_G2") (pintype "passive"))
      (node (ref "J6") (pin "G3") (pinfunction "GND_G3") (pintype "passive"))
      (node (ref "J6") (pin "G4") (pinfunction "POL_G4") (pintype "passive"))
      (node (ref "J6") (pin "P6") (pinfunction "VSS_P6") (pintype "passive"))
      (node (ref "JP2") (pin "1") (pintype "passive"))
      (node (ref "R125") (pin "2") (pinfunction "2_2") (pintype "passive"))
      (node (ref "R126") (pin "2") (pinfunction "2_2") (pintype "passive"))
      (node (ref "R69") (pin "2") (pinfunction "2_2") (pintype "passive"))
      (node (ref "R70") (pin "2") (pinfunction "2_2") (pintype "passive"))
      (node (ref "R71") (pin "2") (pinfunction "2_2") (pintype "passive"))
      (node (ref "R72") (pin "2") (pinfunction "2_2") (pintype "passive"))
      (node (ref "SW1") (pin "2") (pinfunction "2_2") (pintype "passive"))
      (node (ref "SW1") (pin "3") (pinfunction "3_3") (pintype "passive"))
      (node (ref "U11") (pin "2") (pinfunction "GND_2") (pintype "passive"))
      (node (ref "U12") (pin "2") (pinfunction "GND_2") (pintype "power_in"))
      (node (ref "U26") (pin "3") (pinfunction "GND_3") (pintype "passive"))
      (node (ref "U27") (pin "3") (pinfunction "GND_3") (pintype "passive"))
      (node (ref "U28") (pin "3") (pinfunction "GND_3") (pintype "passive"))
      (node (ref "U29") (pin "3") (pinfunction "GND_3") (pintype "passive"))
      (node (ref "U30") (pin "3") (pinfunction "GND_3") (pintype "passive"))
    )
    (net (code "73") (name "Net-(JP2-Pad2)") (class "Default")
      (node (ref "JP2") (pin "2") (pintype "passive"))
      (node (ref "R73") (pin "2") (pinfunction "2_2") (pintype "passive"))
      (node (ref "R76") (pin "2") (pinfunction "2_2") (pintype "passive"))
    )
  )
)
